# HVP_board.net
KiCad netlist of a schematic drawn in EasyEDA
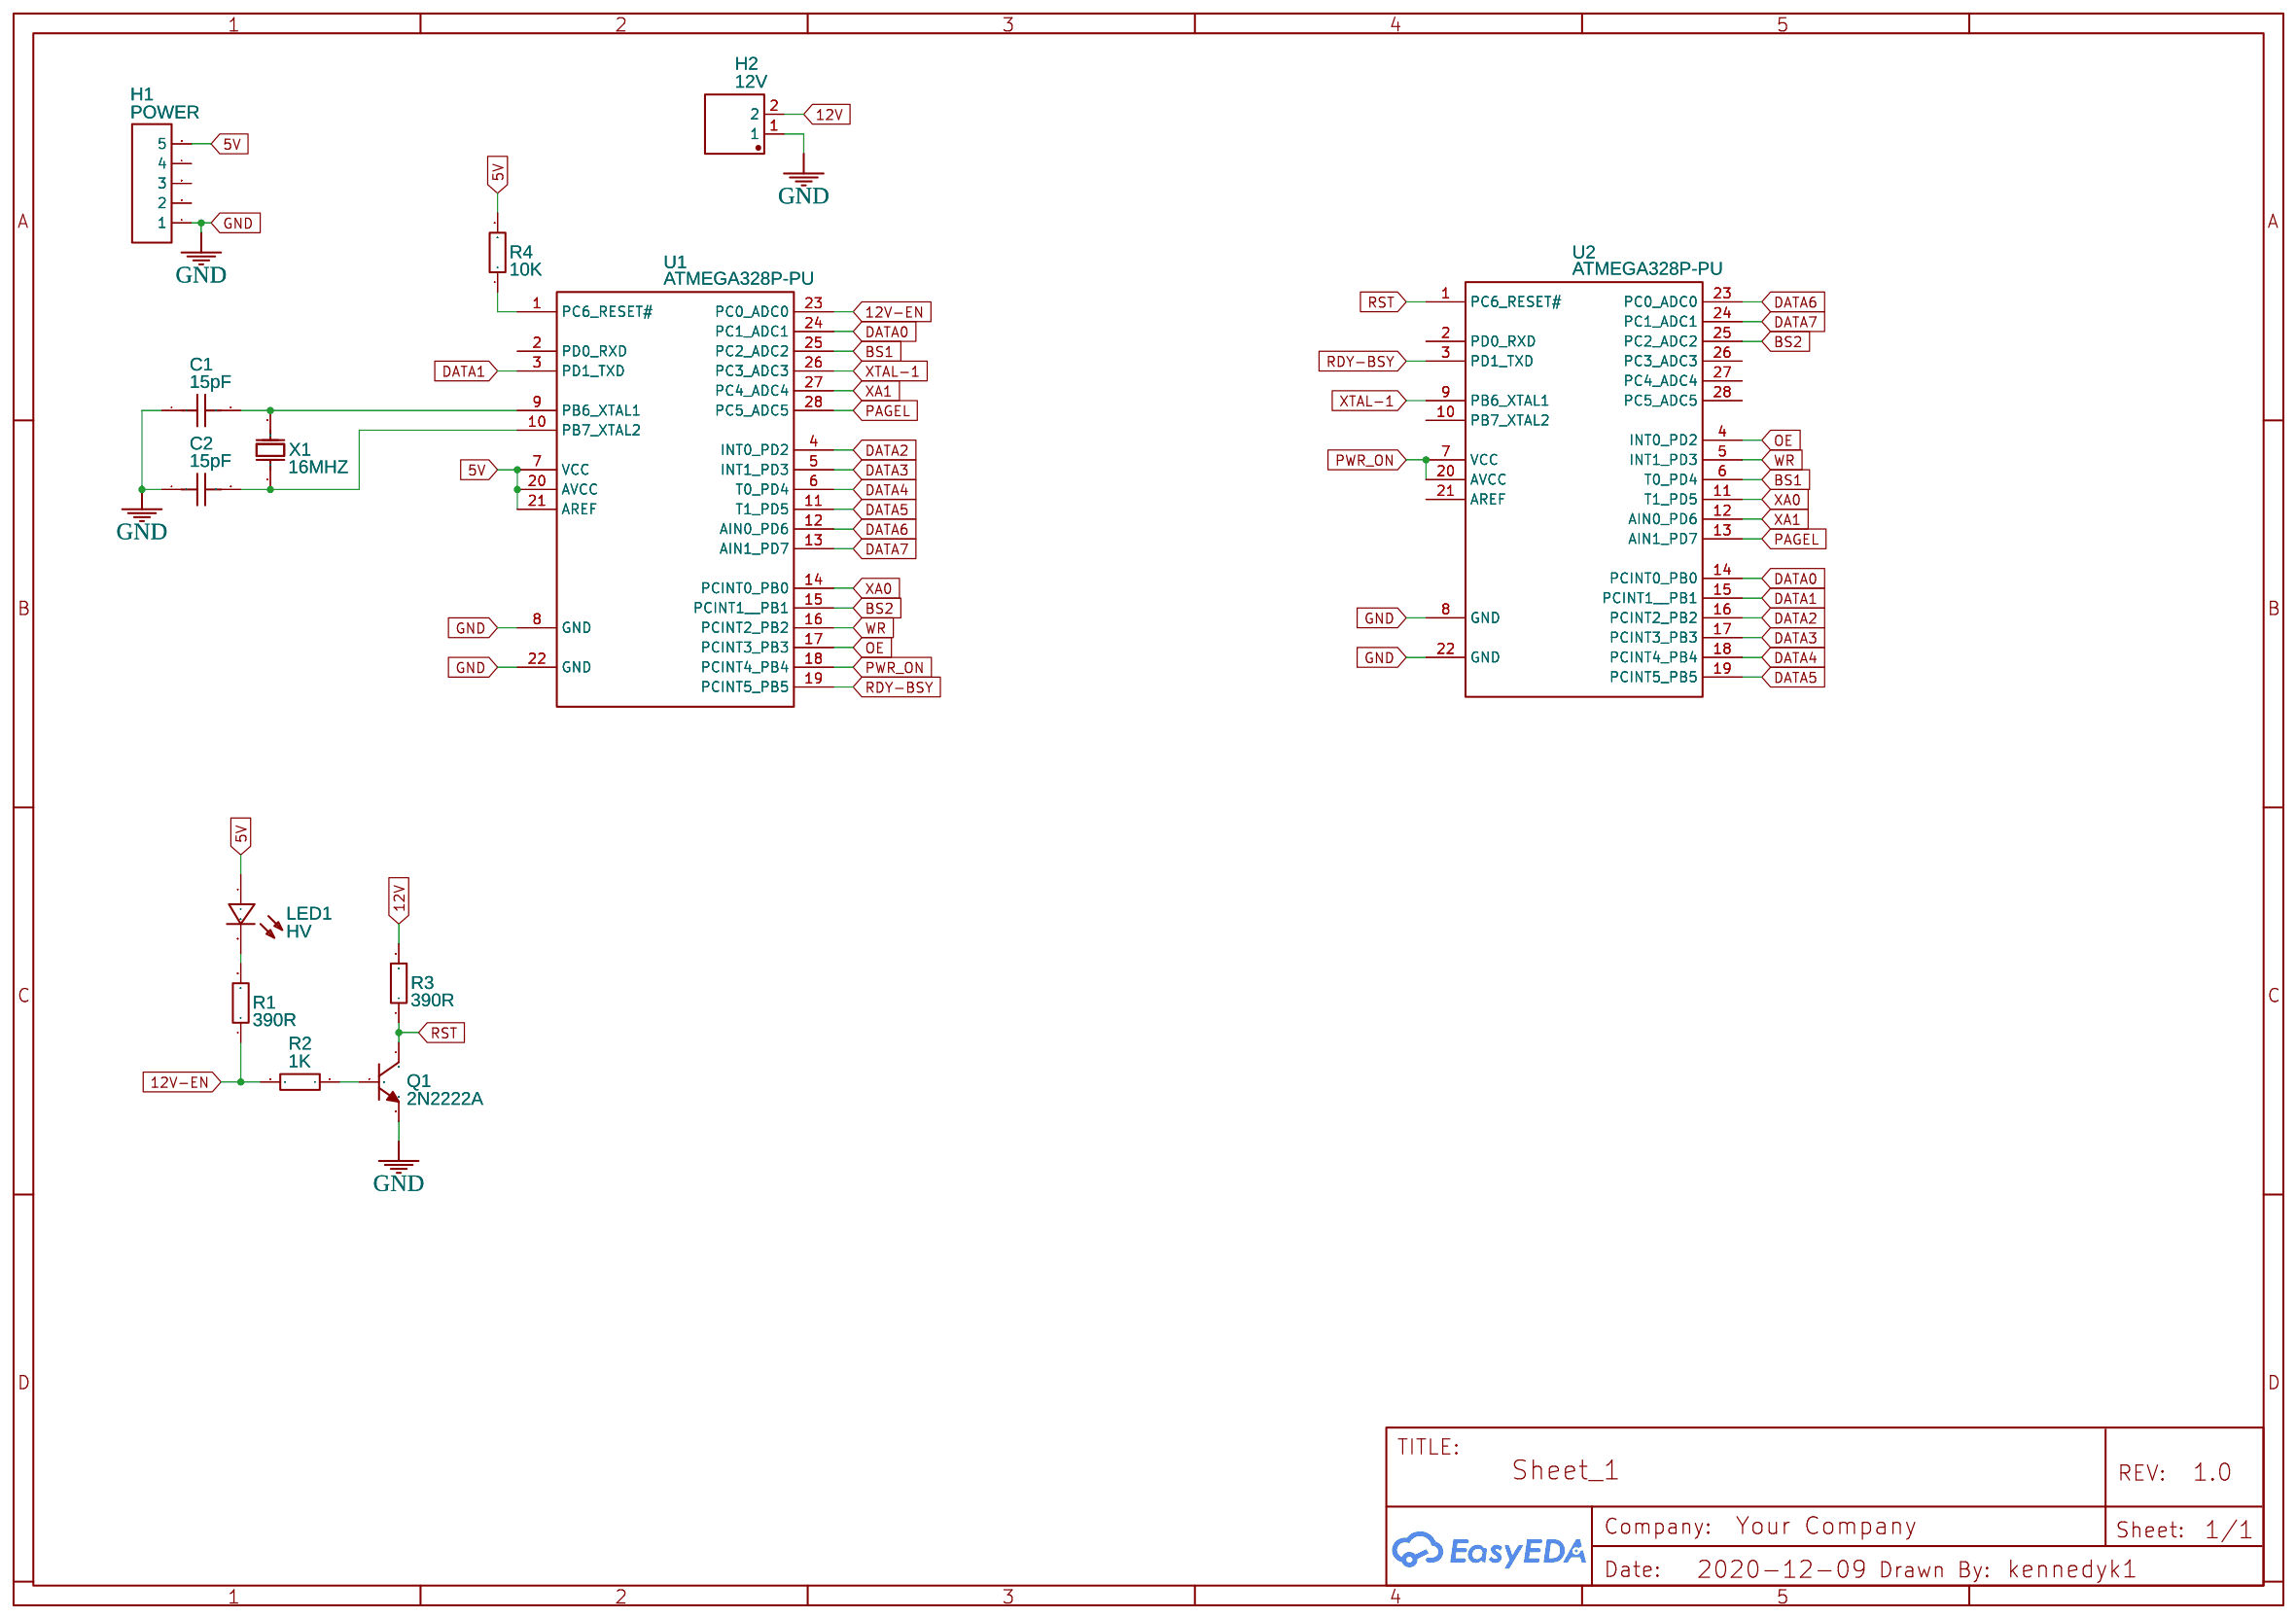
[diagram p0: schematic sheet]

(export (version "E")
  (design (tool "Eeschema 10.0.6"))
  (components
    (comp (ref "C1")
      (value "15pF")
      (fields
        (field (name "BOM_Manufacturer Part") "L06S1B150KN0B0S0N0")
        (field (name "BOM_Supplier Part") "C260719")
      )
      (libsource (lib "") (part "L06S1B150KN0B0S0N0"))
    )
    (comp (ref "C2")
      (value "15pF")
      (fields
        (field (name "BOM_Manufacturer Part") "L06S1B150KN0B0S0N0")
        (field (name "BOM_Supplier Part") "C260719")
      )
      (libsource (lib "") (part "L06S1B150KN0B0S0N0"))
    )
    (comp (ref "H1")
      (value "POWER")
      (fields
        (field (name "BOM_Manufacturer Part") "2.54mm 1*5p Female header")
        (field (name "BOM_Supplier Part") "C50950")
      )
      (libsource (lib "") (part "Header-Female-2.54_1x5"))
    )
    (comp (ref "H2")
      (value "12V")
      (fields
        (field (name "BOM_Manufacturer Part") "68000-102HLF")
        (field (name "BOM_Supplier Part") "C168673")
      )
      (libsource (lib "") (part "68000-102HLF"))
    )
    (comp (ref "LED1")
      (value "HV")
      (fields (field (name "BOM_Manufacturer Part") "HLMP-1719") (field (name "BOM_Supplier Part") "C188721"))
      (libsource (lib "") (part "HLMP-1719"))
    )
    (comp (ref "Q1")
      (value "2N2222A")
      (fields (field (name "BOM_Supplier Part") "C358533"))
      (libsource (lib "") (part "2N2222A"))
    )
    (comp (ref "R1")
      (value "390R")
      (fields
        (field (name "BOM_Manufacturer Part") "CFR0W4J0472A50")
        (field (name "BOM_Supplier Part") "C61297")
      )
      (libsource (lib "") (part "CFR0W4J0472A50"))
    )
    (comp (ref "R2")
      (value "1K")
      (fields
        (field (name "BOM_Manufacturer Part") "CFR0W4J0472A50")
        (field (name "BOM_Supplier Part") "C61297")
      )
      (libsource (lib "") (part "CFR0W4J0472A50_1"))
    )
    (comp (ref "R3")
      (value "390R")
      (fields
        (field (name "BOM_Manufacturer Part") "CFR0W4J0472A50")
        (field (name "BOM_Supplier Part") "C61297")
      )
      (libsource (lib "") (part "CFR0W4J0472A50"))
    )
    (comp (ref "R4")
      (value "10K")
      (fields
        (field (name "BOM_Manufacturer Part") "CFR0W4J0472A50")
        (field (name "BOM_Supplier Part") "C61297")
      )
      (libsource (lib "") (part "CFR0W4J0472A50"))
    )
    (comp (ref "U1")
      (value "ATMEGA328P-PU")
      (fields (field (name "BOM_Supplier Part") "C33901"))
      (libsource (lib "") (part "ATMEGA328P-PU"))
    )
    (comp (ref "U2")
      (value "ATMEGA328P-PU")
      (fields (field (name "BOM_Supplier Part") "C33901"))
      (libsource (lib "") (part "ATMEGA328P-PU"))
    )
    (comp (ref "X1")
      (value "16MHZ")
      (fields
        (field (name "BOM_Manufacturer Part") "49SAC16000202060")
        (field (name "BOM_Supplier Part") "C390745")
      )
      (libsource (lib "") (part "49SAC16000202060"))
    )
  )
  (nets
    (net (code "1") (name "5V") (class "Default")
      (node (ref "H1") (pin "5") (pinfunction "5_5") (pintype "input"))
      (node (ref "LED1") (pin "1") (pinfunction "1_1") (pintype "unspecified"))
      (node (ref "R4") (pin "2") (pinfunction "2_2") (pintype "input"))
      (node (ref "U1") (pin "20") (pinfunction "AVCC_20") (pintype "passive"))
      (node (ref "U1") (pin "21") (pinfunction "AREF_21") (pintype "passive"))
      (node (ref "U1") (pin "7") (pinfunction "VCC_7") (pintype "passive"))
    )
    (net (code "2") (name "12V") (class "Default")
      (node (ref "H2") (pin "2") (pinfunction "2_2") (pintype "unspecified"))
      (node (ref "R3") (pin "2") (pinfunction "2_2") (pintype "input"))
    )
    (net (code "3") (name "12V-EN") (class "Default")
      (node (ref "R1") (pin "1") (pinfunction "1_1") (pintype "input"))
      (node (ref "R2") (pin "2") (pinfunction "2_2") (pintype "input"))
      (node (ref "U1") (pin "23") (pinfunction "PC0_ADC0_23") (pintype "bidirectional"))
    )
    (net (code "4") (name "BS1") (class "Default")
      (node (ref "U1") (pin "25") (pinfunction "PC2_ADC2_25") (pintype "bidirectional"))
      (node (ref "U2") (pin "6") (pinfunction "T0_PD4_6") (pintype "bidirectional"))
    )
    (net (code "5") (name "BS2") (class "Default")
      (node (ref "U1") (pin "15") (pinfunction "PCINT1__PB1_15") (pintype "bidirectional"))
      (node (ref "U2") (pin "25") (pinfunction "PC2_ADC2_25") (pintype "bidirectional"))
    )
    (net (code "6") (name "DATA0") (class "Default")
      (node (ref "U1") (pin "24") (pinfunction "PC1_ADC1_24") (pintype "bidirectional"))
      (node (ref "U2") (pin "14") (pinfunction "PCINT0_PB0_14") (pintype "bidirectional"))
    )
    (net (code "7") (name "DATA1") (class "Default")
      (node (ref "U1") (pin "3") (pinfunction "PD1_TXD_3") (pintype "bidirectional"))
      (node (ref "U2") (pin "15") (pinfunction "PCINT1__PB1_15") (pintype "bidirectional"))
    )
    (net (code "8") (name "DATA2") (class "Default")
      (node (ref "U1") (pin "4") (pinfunction "INT0_PD2_4") (pintype "bidirectional"))
      (node (ref "U2") (pin "16") (pinfunction "PCINT2_PB2_16") (pintype "bidirectional"))
    )
    (net (code "9") (name "DATA3") (class "Default")
      (node (ref "U1") (pin "5") (pinfunction "INT1_PD3_5") (pintype "bidirectional"))
      (node (ref "U2") (pin "17") (pinfunction "PCINT3_PB3_17") (pintype "bidirectional"))
    )
    (net (code "10") (name "DATA4") (class "Default")
      (node (ref "U1") (pin "6") (pinfunction "T0_PD4_6") (pintype "bidirectional"))
      (node (ref "U2") (pin "18") (pinfunction "PCINT4_PB4_18") (pintype "bidirectional"))
    )
    (net (code "11") (name "DATA5") (class "Default")
      (node (ref "U1") (pin "11") (pinfunction "T1_PD5_11") (pintype "bidirectional"))
      (node (ref "U2") (pin "19") (pinfunction "PCINT5_PB5_19") (pintype "bidirectional"))
    )
    (net (code "12") (name "DATA6") (class "Default")
      (node (ref "U1") (pin "12") (pinfunction "AIN0_PD6_12") (pintype "bidirectional"))
      (node (ref "U2") (pin "23") (pinfunction "PC0_ADC0_23") (pintype "bidirectional"))
    )
    (net (code "13") (name "DATA7") (class "Default")
      (node (ref "U1") (pin "13") (pinfunction "AIN1_PD7_13") (pintype "bidirectional"))
      (node (ref "U2") (pin "24") (pinfunction "PC1_ADC1_24") (pintype "bidirectional"))
    )
    (net (code "14") (name "GND") (class "Default")
      (node (ref "C1") (pin "1") (pinfunction "1_1") (pintype "unspecified"))
      (node (ref "C2") (pin "1") (pinfunction "1_1") (pintype "unspecified"))
      (node (ref "H1") (pin "1") (pinfunction "1_1") (pintype "input"))
      (node (ref "H2") (pin "1") (pinfunction "1_1") (pintype "unspecified"))
      (node (ref "Q1") (pin "3") (pinfunction "E_3") (pintype "unspecified"))
      (node (ref "U1") (pin "22") (pinfunction "GND_22") (pintype "passive"))
      (node (ref "U1") (pin "8") (pinfunction "GND_8") (pintype "passive"))
      (node (ref "U2") (pin "22") (pinfunction "GND_22") (pintype "passive"))
      (node (ref "U2") (pin "8") (pinfunction "GND_8") (pintype "passive"))
    )
    (net (code "15") (name "Net-(LED1-Pad2)") (class "Default")
      (node (ref "LED1") (pin "2") (pinfunction "2_2") (pintype "unspecified"))
      (node (ref "R1") (pin "2") (pinfunction "2_2") (pintype "input"))
    )
    (net (code "16") (name "Net-(Q1-B)") (class "Default")
      (node (ref "Q1") (pin "2") (pinfunction "B_2") (pintype "unspecified"))
      (node (ref "R2") (pin "1") (pinfunction "1_1") (pintype "input"))
    )
    (net (code "17") (name "Net-(U1-PB6_XTAL1)") (class "Default")
      (node (ref "C1") (pin "2") (pinfunction "2_2") (pintype "unspecified"))
      (node (ref "U1") (pin "9") (pinfunction "PB6_XTAL1_9") (pintype "bidirectional"))
      (node (ref "X1") (pin "2") (pinfunction "OSC2_2") (pintype "input"))
    )
    (net (code "18") (name "Net-(U1-PB7_XTAL2)") (class "Default")
      (node (ref "C2") (pin "2") (pinfunction "2_2") (pintype "unspecified"))
      (node (ref "U1") (pin "10") (pinfunction "PB7_XTAL2_10") (pintype "bidirectional"))
      (node (ref "X1") (pin "1") (pinfunction "OSC1_1") (pintype "input"))
    )
    (net (code "19") (name "Net-(U1-PC6_RESET#)") (class "Default")
      (node (ref "R4") (pin "1") (pinfunction "1_1") (pintype "input"))
      (node (ref "U1") (pin "1") (pinfunction "PC6_RESET#_1") (pintype "bidirectional"))
    )
    (net (code "20") (name "OE") (class "Default")
      (node (ref "U1") (pin "17") (pinfunction "PCINT3_PB3_17") (pintype "bidirectional"))
      (node (ref "U2") (pin "4") (pinfunction "INT0_PD2_4") (pintype "bidirectional"))
    )
    (net (code "21") (name "PAGEL") (class "Default")
      (node (ref "U1") (pin "28") (pinfunction "PC5_ADC5_28") (pintype "bidirectional"))
      (node (ref "U2") (pin "13") (pinfunction "AIN1_PD7_13") (pintype "bidirectional"))
    )
    (net (code "22") (name "PWR_ON") (class "Default")
      (node (ref "U1") (pin "18") (pinfunction "PCINT4_PB4_18") (pintype "bidirectional"))
      (node (ref "U2") (pin "20") (pinfunction "AVCC_20") (pintype "passive"))
      (node (ref "U2") (pin "7") (pinfunction "VCC_7") (pintype "passive"))
    )
    (net (code "23") (name "RDY-BSY") (class "Default")
      (node (ref "U1") (pin "19") (pinfunction "PCINT5_PB5_19") (pintype "bidirectional"))
      (node (ref "U2") (pin "3") (pinfunction "PD1_TXD_3") (pintype "bidirectional"))
    )
    (net (code "24") (name "RST") (class "Default")
      (node (ref "Q1") (pin "1") (pinfunction "C_1") (pintype "unspecified"))
      (node (ref "R3") (pin "1") (pinfunction "1_1") (pintype "input"))
      (node (ref "U2") (pin "1") (pinfunction "PC6_RESET#_1") (pintype "bidirectional"))
    )
    (net (code "25") (name "WR") (class "Default")
      (node (ref "U1") (pin "16") (pinfunction "PCINT2_PB2_16") (pintype "bidirectional"))
      (node (ref "U2") (pin "5") (pinfunction "INT1_PD3_5") (pintype "bidirectional"))
    )
    (net (code "26") (name "XA0") (class "Default")
      (node (ref "U1") (pin "14") (pinfunction "PCINT0_PB0_14") (pintype "bidirectional"))
      (node (ref "U2") (pin "11") (pinfunction "T1_PD5_11") (pintype "bidirectional"))
    )
    (net (code "27") (name "XA1") (class "Default")
      (node (ref "U1") (pin "27") (pinfunction "PC4_ADC4_27") (pintype "bidirectional"))
      (node (ref "U2") (pin "12") (pinfunction "AIN0_PD6_12") (pintype "bidirectional"))
    )
    (net (code "28") (name "XTAL-1") (class "Default")
      (node (ref "U1") (pin "26") (pinfunction "PC3_ADC3_26") (pintype "bidirectional"))
      (node (ref "U2") (pin "9") (pinfunction "PB6_XTAL1_9") (pintype "bidirectional"))
    )
    (net (code "29") (name "unconnected-(H1-Pad2)") (class "Default")
      (node (ref "H1") (pin "2") (pinfunction "2_2") (pintype "input"))
    )
    (net (code "30") (name "unconnected-(H1-Pad3)") (class "Default")
      (node (ref "H1") (pin "3") (pinfunction "3_3") (pintype "input"))
    )
    (net (code "31") (name "unconnected-(H1-Pad4)") (class "Default")
      (node (ref "H1") (pin "4") (pinfunction "4_4") (pintype "input"))
    )
    (net (code "32") (name "unconnected-(U1-PD0_RXD-Pad2)") (class "Default")
      (node (ref "U1") (pin "2") (pinfunction "PD0_RXD_2") (pintype "bidirectional"))
    )
    (net (code "33") (name "unconnected-(U2-AREF-Pad21)") (class "Default")
      (node (ref "U2") (pin "21") (pinfunction "AREF_21") (pintype "passive"))
    )
    (net (code "34") (name "unconnected-(U2-PB7_XTAL2-Pad10)") (class "Default")
      (node (ref "U2") (pin "10") (pinfunction "PB7_XTAL2_10") (pintype "bidirectional"))
    )
    (net (code "35") (name "unconnected-(U2-PC3_ADC3-Pad26)") (class "Default")
      (node (ref "U2") (pin "26") (pinfunction "PC3_ADC3_26") (pintype "bidirectional"))
    )
    (net (code "36") (name "unconnected-(U2-PC4_ADC4-Pad27)") (class "Default")
      (node (ref "U2") (pin "27") (pinfunction "PC4_ADC4_27") (pintype "bidirectional"))
    )
    (net (code "37") (name "unconnected-(U2-PC5_ADC5-Pad28)") (class "Default")
      (node (ref "U2") (pin "28") (pinfunction "PC5_ADC5_28") (pintype "bidirectional"))
    )
    (net (code "38") (name "unconnected-(U2-PD0_RXD-Pad2)") (class "Default")
      (node (ref "U2") (pin "2") (pinfunction "PD0_RXD_2") (pintype "bidirectional"))
    )
  )
)
